# Bending_Machine_SCH.net
KiCad netlist of a schematic drawn in Altium Designer
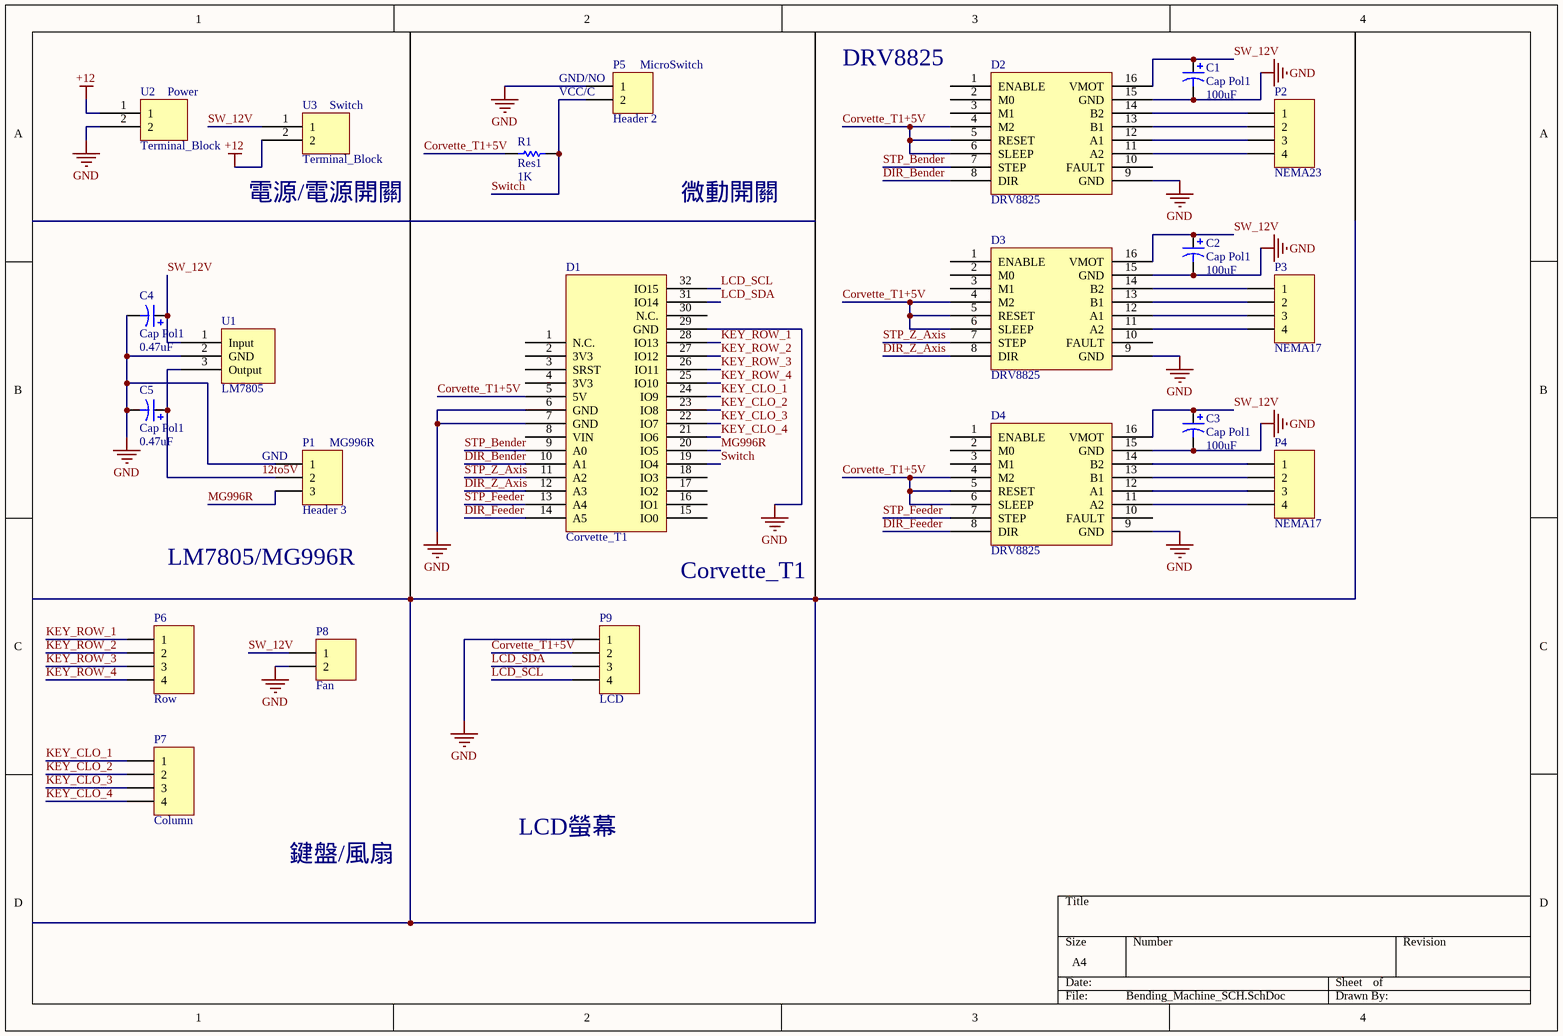
[diagram p0: Bending_Machine_SCH.SchDoc]

(export (version "E")
  (design (tool "Eeschema 10.0.6"))
  (components
    (comp (ref "C1")
      (value "Cap Pol1")
      (footprint "Cap_100uF")
      (description "Polarized Capacitor (Radial)")
      (fields (field (name "ALTIUM_VALUE") "100uF") (field (name "PUBLISHER") "Altium Limited"))
      (libsource (lib "Miscellaneous Devices") (part "Cap Pol1"))
    )
    (comp (ref "C2")
      (value "Cap Pol1")
      (footprint "Cap_100uF")
      (description "Polarized Capacitor (Radial)")
      (fields (field (name "ALTIUM_VALUE") "100uF") (field (name "PUBLISHER") "Altium Limited"))
      (libsource (lib "Miscellaneous Devices") (part "Cap Pol1"))
    )
    (comp (ref "C3")
      (value "Cap Pol1")
      (footprint "Cap_100uF")
      (description "Polarized Capacitor (Radial)")
      (fields (field (name "ALTIUM_VALUE") "100uF") (field (name "PUBLISHER") "Altium Limited"))
      (libsource (lib "Miscellaneous Devices") (part "Cap Pol1"))
    )
    (comp (ref "C4")
      (value "Cap Pol1")
      (footprint "Cap_0.47uF")
      (description "Polarized Capacitor (Radial)")
      (fields (field (name "ALTIUM_VALUE") "0.47uF") (field (name "PUBLISHER") "Altium Limited"))
      (libsource (lib "Miscellaneous Devices") (part "Cap Pol1"))
    )
    (comp (ref "C5")
      (value "Cap Pol1")
      (footprint "Cap_0.47uF")
      (description "Polarized Capacitor (Radial)")
      (fields (field (name "ALTIUM_VALUE") "0.47uF") (field (name "PUBLISHER") "Altium Limited"))
      (libsource (lib "Miscellaneous Devices") (part "Cap Pol1"))
    )
    (comp (ref "D1")
      (value "Corvette_T1")
      (footprint "Corvette_T1")
      (libsource (lib "Bending_Machine") (part "Corvette_T1"))
    )
    (comp (ref "D2")
      (value "DRV8825")
      (footprint "DRV8825")
      (libsource (lib "Bending_Machine") (part "DRV8825"))
    )
    (comp (ref "D3")
      (value "DRV8825")
      (footprint "DRV8825")
      (libsource (lib "Bending_Machine") (part "DRV8825"))
    )
    (comp (ref "D4")
      (value "DRV8825")
      (footprint "DRV8825")
      (libsource (lib "Bending_Machine") (part "DRV8825"))
    )
    (comp (ref "P1")
      (value "Header 3")
      (footprint "HDR1X3")
      (description "Header, 3-Pin")
      (fields (field (name "PUBLISHER") "Altium Limited"))
      (libsource (lib "Miscellaneous Connectors") (part "Header 3"))
    )
    (comp (ref "P2")
      (value "NEMA23")
      (footprint "HDR1X4")
      (description "Header, 4-Pin")
      (fields (field (name "PUBLISHER") "Altium Limited"))
      (libsource (lib "Miscellaneous Connectors") (part "Header 4"))
    )
    (comp (ref "P3")
      (value "NEMA17")
      (footprint "HDR1X4")
      (description "Header, 4-Pin")
      (fields (field (name "PUBLISHER") "Altium Limited"))
      (libsource (lib "Miscellaneous Connectors") (part "Header 4"))
    )
    (comp (ref "P4")
      (value "NEMA17")
      (footprint "HDR1X4")
      (description "Header, 4-Pin")
      (fields (field (name "PUBLISHER") "Altium Limited"))
      (libsource (lib "Miscellaneous Connectors") (part "Header 4"))
    )
    (comp (ref "P5")
      (value "Header 2")
      (footprint "HDR1X2")
      (description "Header, 2-Pin")
      (fields (field (name "PUBLISHER") "Altium Limited"))
      (libsource (lib "Miscellaneous Connectors") (part "Header 2"))
    )
    (comp (ref "P6")
      (value "Row")
      (footprint "HDR1X4")
      (description "Header, 4-Pin")
      (fields (field (name "PUBLISHER") "Altium Limited"))
      (libsource (lib "Miscellaneous Connectors") (part "Header 4"))
    )
    (comp (ref "P7")
      (value "Column")
      (footprint "HDR1X4")
      (description "Header, 4-Pin")
      (fields (field (name "PUBLISHER") "Altium Limited"))
      (libsource (lib "Miscellaneous Connectors") (part "Header 4"))
    )
    (comp (ref "P8")
      (value "Fan")
      (footprint "HDR1X2")
      (description "Header, 2-Pin")
      (fields (field (name "PUBLISHER") "Altium Limited"))
      (libsource (lib "Miscellaneous Connectors") (part "Header 2"))
    )
    (comp (ref "P9")
      (value "LCD")
      (footprint "HDR1X4")
      (description "Header, 4-Pin")
      (fields (field (name "PUBLISHER") "Altium Limited"))
      (libsource (lib "Miscellaneous Connectors") (part "Header 4"))
    )
    (comp (ref "R1")
      (value "Res1")
      (footprint "AXIAL-0.3")
      (description "Resistor")
      (fields (field (name "ALTIUM_VALUE") "1K") (field (name "PUBLISHER") "Altium Limited"))
      (libsource (lib "Miscellaneous Devices") (part "Res1"))
    )
    (comp (ref "U1")
      (value "LM7805")
      (footprint "LM7805")
      (libsource (lib "Bending_Machine") (part "LM7805"))
    )
    (comp (ref "U2")
      (value "Terminal_Block")
      (footprint "terminal block")
      (libsource (lib "Bending_Machine") (part "Terminal Block"))
    )
    (comp (ref "U3")
      (value "Terminal_Block")
      (footprint "terminal block")
      (libsource (lib "Bending_Machine") (part "Terminal Block"))
    )
  )
  (nets
    (net (code "1") (name "+12") (class "Default")
      (node (ref "U2") (pin "1") (pinfunction "1_1") (pintype "passive"))
      (node (ref "U3") (pin "2") (pinfunction "2_2") (pintype "passive"))
    )
    (net (code "2") (name "/12to5V") (class "Default")
      (node (ref "C5") (pin "1") (pinfunction "1_1") (pintype "passive"))
      (node (ref "P1") (pin "2") (pinfunction "2_2") (pintype "passive"))
      (node (ref "U1") (pin "3") (pinfunction "Output_3") (pintype "passive"))
    )
    (net (code "3") (name "/Corvette_T1+5V") (class "Default")
      (node (ref "D1") (pin "5") (pinfunction "5V_5") (pintype "passive"))
      (node (ref "D2") (pin "4") (pinfunction "M2_4") (pintype "passive"))
      (node (ref "D2") (pin "5") (pinfunction "RESET_5") (pintype "passive"))
      (node (ref "D2") (pin "6") (pinfunction "SLEEP_6") (pintype "passive"))
      (node (ref "D3") (pin "4") (pinfunction "M2_4") (pintype "passive"))
      (node (ref "D3") (pin "5") (pinfunction "RESET_5") (pintype "passive"))
      (node (ref "D3") (pin "6") (pinfunction "SLEEP_6") (pintype "passive"))
      (node (ref "D4") (pin "4") (pinfunction "M2_4") (pintype "passive"))
      (node (ref "D4") (pin "5") (pinfunction "RESET_5") (pintype "passive"))
      (node (ref "D4") (pin "6") (pinfunction "SLEEP_6") (pintype "passive"))
      (node (ref "P9") (pin "2") (pinfunction "2_2") (pintype "passive"))
      (node (ref "R1") (pin "1") (pinfunction "1_1") (pintype "passive"))
    )
    (net (code "4") (name "/DIR_Bender") (class "Default")
      (node (ref "D1") (pin "10") (pinfunction "A1_10") (pintype "passive"))
      (node (ref "D2") (pin "8") (pinfunction "DIR_8") (pintype "passive"))
    )
    (net (code "5") (name "/DIR_Feeder") (class "Default")
      (node (ref "D1") (pin "14") (pinfunction "A5_14") (pintype "passive"))
      (node (ref "D4") (pin "8") (pinfunction "DIR_8") (pintype "passive"))
    )
    (net (code "6") (name "/DIR_Z_Axis") (class "Default")
      (node (ref "D1") (pin "12") (pinfunction "A3_12") (pintype "passive"))
      (node (ref "D3") (pin "8") (pinfunction "DIR_8") (pintype "passive"))
    )
    (net (code "7") (name "/KEY_CLO_1") (class "Default")
      (node (ref "D1") (pin "24") (pinfunction "IO9_24") (pintype "passive"))
      (node (ref "P7") (pin "1") (pinfunction "1_1") (pintype "passive"))
    )
    (net (code "8") (name "/KEY_CLO_2") (class "Default")
      (node (ref "D1") (pin "23") (pinfunction "IO8_23") (pintype "passive"))
      (node (ref "P7") (pin "2") (pinfunction "2_2") (pintype "passive"))
    )
    (net (code "9") (name "/KEY_CLO_3") (class "Default")
      (node (ref "D1") (pin "22") (pinfunction "IO7_22") (pintype "passive"))
      (node (ref "P7") (pin "3") (pinfunction "3_3") (pintype "passive"))
    )
    (net (code "10") (name "/KEY_CLO_4") (class "Default")
      (node (ref "D1") (pin "21") (pinfunction "IO6_21") (pintype "passive"))
      (node (ref "P7") (pin "4") (pinfunction "4_4") (pintype "passive"))
    )
    (net (code "11") (name "/KEY_ROW_1") (class "Default")
      (node (ref "D1") (pin "28") (pinfunction "IO13_28") (pintype "passive"))
      (node (ref "P6") (pin "1") (pinfunction "1_1") (pintype "passive"))
    )
    (net (code "12") (name "/KEY_ROW_2") (class "Default")
      (node (ref "D1") (pin "27") (pinfunction "IO12_27") (pintype "passive"))
      (node (ref "P6") (pin "2") (pinfunction "2_2") (pintype "passive"))
    )
    (net (code "13") (name "/KEY_ROW_3") (class "Default")
      (node (ref "D1") (pin "26") (pinfunction "IO11_26") (pintype "passive"))
      (node (ref "P6") (pin "3") (pinfunction "3_3") (pintype "passive"))
    )
    (net (code "14") (name "/KEY_ROW_4") (class "Default")
      (node (ref "D1") (pin "25") (pinfunction "IO10_25") (pintype "passive"))
      (node (ref "P6") (pin "4") (pinfunction "4_4") (pintype "passive"))
    )
    (net (code "15") (name "/LCD_SCL") (class "Default")
      (node (ref "D1") (pin "32") (pinfunction "IO15_32") (pintype "passive"))
      (node (ref "P9") (pin "4") (pinfunction "4_4") (pintype "passive"))
    )
    (net (code "16") (name "/LCD_SDA") (class "Default")
      (node (ref "D1") (pin "31") (pinfunction "IO14_31") (pintype "passive"))
      (node (ref "P9") (pin "3") (pinfunction "3_3") (pintype "passive"))
    )
    (net (code "17") (name "/MG996R") (class "Default")
      (node (ref "D1") (pin "20") (pinfunction "IO5_20") (pintype "passive"))
      (node (ref "P1") (pin "3") (pinfunction "3_3") (pintype "passive"))
    )
    (net (code "18") (name "/STP_Bender") (class "Default")
      (node (ref "D1") (pin "9") (pinfunction "A0_9") (pintype "passive"))
      (node (ref "D2") (pin "7") (pinfunction "STEP_7") (pintype "passive"))
    )
    (net (code "19") (name "/STP_Feeder") (class "Default")
      (node (ref "D1") (pin "13") (pinfunction "A4_13") (pintype "passive"))
      (node (ref "D4") (pin "7") (pinfunction "STEP_7") (pintype "passive"))
    )
    (net (code "20") (name "/STP_Z_Axis") (class "Default")
      (node (ref "D1") (pin "11") (pinfunction "A2_11") (pintype "passive"))
      (node (ref "D3") (pin "7") (pinfunction "STEP_7") (pintype "passive"))
    )
    (net (code "21") (name "/SW_12V") (class "Default")
      (node (ref "C1") (pin "1") (pinfunction "1_1") (pintype "passive"))
      (node (ref "C2") (pin "1") (pinfunction "1_1") (pintype "passive"))
      (node (ref "C3") (pin "1") (pinfunction "1_1") (pintype "passive"))
      (node (ref "C4") (pin "1") (pinfunction "1_1") (pintype "passive"))
      (node (ref "D2") (pin "16") (pinfunction "VMOT_16") (pintype "passive"))
      (node (ref "D3") (pin "16") (pinfunction "VMOT_16") (pintype "passive"))
      (node (ref "D4") (pin "16") (pinfunction "VMOT_16") (pintype "passive"))
      (node (ref "P8") (pin "1") (pinfunction "1_1") (pintype "passive"))
      (node (ref "U1") (pin "1") (pinfunction "Input_1") (pintype "passive"))
      (node (ref "U3") (pin "1") (pinfunction "1_1") (pintype "passive"))
    )
    (net (code "22") (name "/Switch") (class "Default")
      (node (ref "D1") (pin "19") (pinfunction "IO4_19") (pintype "passive"))
      (node (ref "P5") (pin "2") (pinfunction "2_2") (pintype "passive"))
      (node (ref "R1") (pin "2") (pinfunction "2_2") (pintype "passive"))
    )
    (net (code "23") (name "GND") (class "Default")
      (node (ref "C1") (pin "2") (pinfunction "2_2") (pintype "passive"))
      (node (ref "C2") (pin "2") (pinfunction "2_2") (pintype "passive"))
      (node (ref "C3") (pin "2") (pinfunction "2_2") (pintype "passive"))
      (node (ref "C4") (pin "2") (pinfunction "2_2") (pintype "passive"))
      (node (ref "C5") (pin "2") (pinfunction "2_2") (pintype "passive"))
      (node (ref "D1") (pin "29") (pinfunction "GND_29") (pintype "passive"))
      (node (ref "D1") (pin "6") (pinfunction "GND_6") (pintype "passive"))
      (node (ref "D1") (pin "7") (pinfunction "GND_7") (pintype "passive"))
      (node (ref "D2") (pin "15") (pinfunction "GND_15") (pintype "passive"))
      (node (ref "D2") (pin "9") (pinfunction "GND_9") (pintype "passive"))
      (node (ref "D3") (pin "15") (pinfunction "GND_15") (pintype "passive"))
      (node (ref "D3") (pin "9") (pinfunction "GND_9") (pintype "passive"))
      (node (ref "D4") (pin "15") (pinfunction "GND_15") (pintype "passive"))
      (node (ref "D4") (pin "9") (pinfunction "GND_9") (pintype "passive"))
      (node (ref "P1") (pin "1") (pinfunction "1_1") (pintype "passive"))
      (node (ref "P5") (pin "1") (pinfunction "1_1") (pintype "passive"))
      (node (ref "P8") (pin "2") (pinfunction "2_2") (pintype "passive"))
      (node (ref "P9") (pin "1") (pinfunction "1_1") (pintype "passive"))
      (node (ref "U1") (pin "2") (pinfunction "GND_2") (pintype "passive"))
      (node (ref "U2") (pin "2") (pinfunction "2_2") (pintype "passive"))
    )
    (net (code "24") (name "Net-(D2-A1)") (class "Default")
      (node (ref "D2") (pin "12") (pinfunction "A1_12") (pintype "passive"))
      (node (ref "P2") (pin "3") (pinfunction "3_3") (pintype "passive"))
    )
    (net (code "25") (name "Net-(D2-A2)") (class "Default")
      (node (ref "D2") (pin "11") (pinfunction "A2_11") (pintype "passive"))
      (node (ref "P2") (pin "4") (pinfunction "4_4") (pintype "passive"))
    )
    (net (code "26") (name "Net-(D2-B1)") (class "Default")
      (node (ref "D2") (pin "13") (pinfunction "B1_13") (pintype "passive"))
      (node (ref "P2") (pin "2") (pinfunction "2_2") (pintype "passive"))
    )
    (net (code "27") (name "Net-(D2-B2)") (class "Default")
      (node (ref "D2") (pin "14") (pinfunction "B2_14") (pintype "passive"))
      (node (ref "P2") (pin "1") (pinfunction "1_1") (pintype "passive"))
    )
    (net (code "28") (name "Net-(D3-A1)") (class "Default")
      (node (ref "D3") (pin "12") (pinfunction "A1_12") (pintype "passive"))
      (node (ref "P3") (pin "3") (pinfunction "3_3") (pintype "passive"))
    )
    (net (code "29") (name "Net-(D3-A2)") (class "Default")
      (node (ref "D3") (pin "11") (pinfunction "A2_11") (pintype "passive"))
      (node (ref "P3") (pin "4") (pinfunction "4_4") (pintype "passive"))
    )
    (net (code "30") (name "Net-(D3-B1)") (class "Default")
      (node (ref "D3") (pin "13") (pinfunction "B1_13") (pintype "passive"))
      (node (ref "P3") (pin "2") (pinfunction "2_2") (pintype "passive"))
    )
    (net (code "31") (name "Net-(D3-B2)") (class "Default")
      (node (ref "D3") (pin "14") (pinfunction "B2_14") (pintype "passive"))
      (node (ref "P3") (pin "1") (pinfunction "1_1") (pintype "passive"))
    )
    (net (code "32") (name "Net-(D4-A1)") (class "Default")
      (node (ref "D4") (pin "12") (pinfunction "A1_12") (pintype "passive"))
      (node (ref "P4") (pin "3") (pinfunction "3_3") (pintype "passive"))
    )
    (net (code "33") (name "Net-(D4-A2)") (class "Default")
      (node (ref "D4") (pin "11") (pinfunction "A2_11") (pintype "passive"))
      (node (ref "P4") (pin "4") (pinfunction "4_4") (pintype "passive"))
    )
    (net (code "34") (name "Net-(D4-B1)") (class "Default")
      (node (ref "D4") (pin "13") (pinfunction "B1_13") (pintype "passive"))
      (node (ref "P4") (pin "2") (pinfunction "2_2") (pintype "passive"))
    )
    (net (code "35") (name "Net-(D4-B2)") (class "Default")
      (node (ref "D4") (pin "14") (pinfunction "B2_14") (pintype "passive"))
      (node (ref "P4") (pin "1") (pinfunction "1_1") (pintype "passive"))
    )
    (net (code "36") (name "unconnected-(D1-3V3-Pad2)") (class "Default")
      (node (ref "D1") (pin "2") (pinfunction "3V3_2") (pintype "passive"))
    )
    (net (code "37") (name "unconnected-(D1-3V3-Pad4)") (class "Default")
      (node (ref "D1") (pin "4") (pinfunction "3V3_4") (pintype "passive"))
    )
    (net (code "38") (name "unconnected-(D1-IO0-Pad15)") (class "Default")
      (node (ref "D1") (pin "15") (pinfunction "IO0_15") (pintype "passive"))
    )
    (net (code "39") (name "unconnected-(D1-IO1-Pad16)") (class "Default")
      (node (ref "D1") (pin "16") (pinfunction "IO1_16") (pintype "passive"))
    )
    (net (code "40") (name "unconnected-(D1-IO2-Pad17)") (class "Default")
      (node (ref "D1") (pin "17") (pinfunction "IO2_17") (pintype "passive"))
    )
    (net (code "41") (name "unconnected-(D1-IO3-Pad18)") (class "Default")
      (node (ref "D1") (pin "18") (pinfunction "IO3_18") (pintype "passive"))
    )
    (net (code "42") (name "unconnected-(D1-N.C.-Pad1)") (class "Default")
      (node (ref "D1") (pin "1") (pinfunction "N.C._1") (pintype "passive"))
    )
    (net (code "43") (name "unconnected-(D1-N.C.-Pad30)") (class "Default")
      (node (ref "D1") (pin "30") (pinfunction "N.C._30") (pintype "passive"))
    )
    (net (code "44") (name "unconnected-(D1-SRST-Pad3)") (class "Default")
      (node (ref "D1") (pin "3") (pinfunction "SRST_3") (pintype "passive"))
    )
    (net (code "45") (name "unconnected-(D1-VIN-Pad8)") (class "Default")
      (node (ref "D1") (pin "8") (pinfunction "VIN_8") (pintype "passive"))
    )
    (net (code "46") (name "unconnected-(D2-ENABLE-Pad1)") (class "Default")
      (node (ref "D2") (pin "1") (pinfunction "ENABLE_1") (pintype "passive"))
    )
    (net (code "47") (name "unconnected-(D2-FAULT-Pad10)") (class "Default")
      (node (ref "D2") (pin "10") (pinfunction "FAULT_10") (pintype "passive"))
    )
    (net (code "48") (name "unconnected-(D2-M0-Pad2)") (class "Default")
      (node (ref "D2") (pin "2") (pinfunction "M0_2") (pintype "passive"))
    )
    (net (code "49") (name "unconnected-(D2-M1-Pad3)") (class "Default")
      (node (ref "D2") (pin "3") (pinfunction "M1_3") (pintype "passive"))
    )
    (net (code "50") (name "unconnected-(D3-ENABLE-Pad1)") (class "Default")
      (node (ref "D3") (pin "1") (pinfunction "ENABLE_1") (pintype "passive"))
    )
    (net (code "51") (name "unconnected-(D3-FAULT-Pad10)") (class "Default")
      (node (ref "D3") (pin "10") (pinfunction "FAULT_10") (pintype "passive"))
    )
    (net (code "52") (name "unconnected-(D3-M0-Pad2)") (class "Default")
      (node (ref "D3") (pin "2") (pinfunction "M0_2") (pintype "passive"))
    )
    (net (code "53") (name "unconnected-(D3-M1-Pad3)") (class "Default")
      (node (ref "D3") (pin "3") (pinfunction "M1_3") (pintype "passive"))
    )
    (net (code "54") (name "unconnected-(D4-ENABLE-Pad1)") (class "Default")
      (node (ref "D4") (pin "1") (pinfunction "ENABLE_1") (pintype "passive"))
    )
    (net (code "55") (name "unconnected-(D4-FAULT-Pad10)") (class "Default")
      (node (ref "D4") (pin "10") (pinfunction "FAULT_10") (pintype "passive"))
    )
    (net (code "56") (name "unconnected-(D4-M0-Pad2)") (class "Default")
      (node (ref "D4") (pin "2") (pinfunction "M0_2") (pintype "passive"))
    )
    (net (code "57") (name "unconnected-(D4-M1-Pad3)") (class "Default")
      (node (ref "D4") (pin "3") (pinfunction "M1_3") (pintype "passive"))
    )
  )
)
